# shema.net
KiCad netlist of a schematic drawn in EAGLE
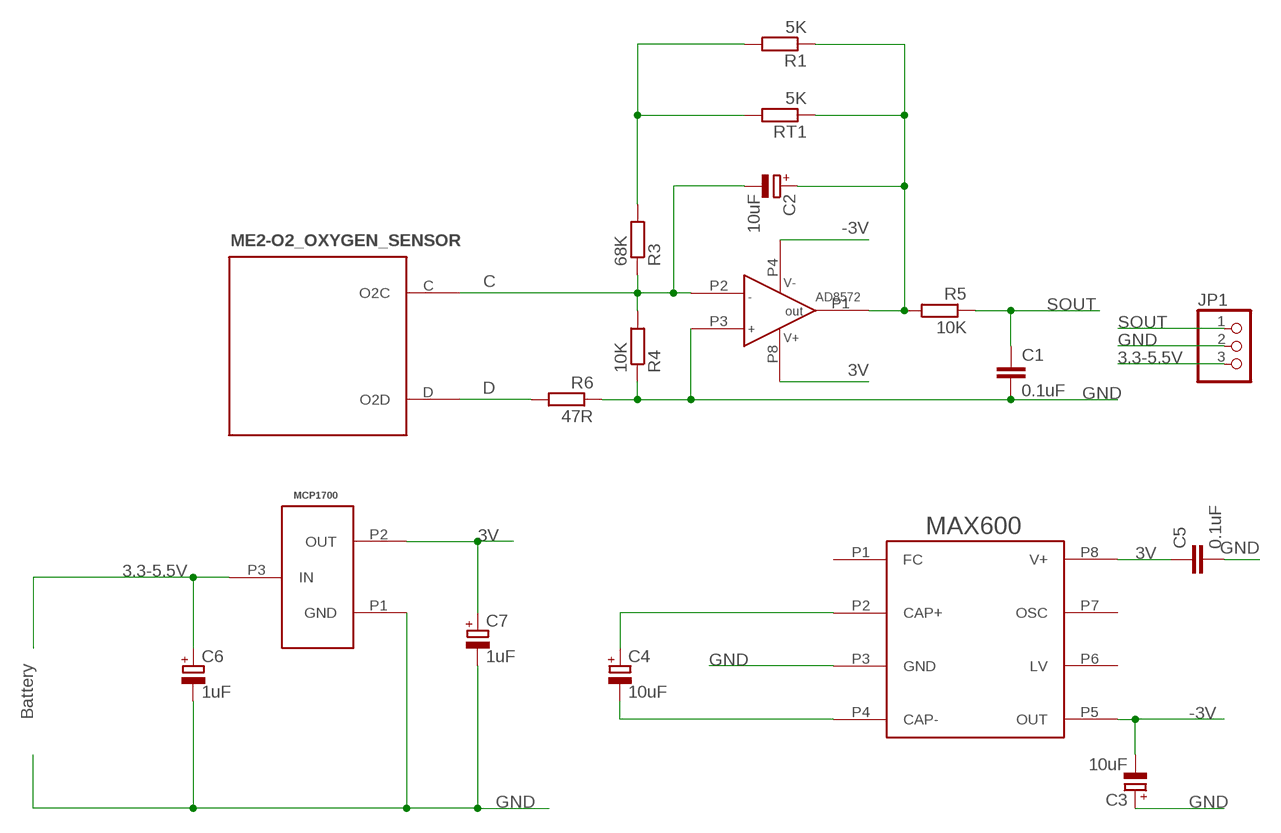
[diagram p0: schematic, sheet 1]

(export (version "E")
  (design (tool "Eeschema 10.0.6"))
  (components
    (comp (ref "AD8572")
      (value "AD8572")
      (footprint "eagle-import:AD8572")
      (libsource (lib "eagle-import") (part "AD8572"))
    )
    (comp (ref "C1")
      (value "0.1uF")
      (footprint "eagle-import:C0603")
      (libsource (lib "eagle-import") (part "C-EUC0603"))
    )
    (comp (ref "C2")
      (value "10uF")
      (footprint "eagle-import:153CLV-0405")
      (libsource (lib "eagle-import") (part "CPOL-EU153CLV-0405"))
    )
    (comp (ref "C3")
      (value "10uF")
      (footprint "eagle-import:153CLV-0405")
      (libsource (lib "eagle-import") (part "CPOL-EU153CLV-0405"))
    )
    (comp (ref "C4")
      (value "10uF")
      (footprint "eagle-import:153CLV-0405")
      (libsource (lib "eagle-import") (part "CPOL-EU153CLV-0405"))
    )
    (comp (ref "C5")
      (value "0.1uF")
      (footprint "eagle-import:C0603")
      (libsource (lib "eagle-import") (part "C-EUC0603"))
    )
    (comp (ref "C6")
      (value "1uF")
      (footprint "eagle-import:153CLV-0405")
      (libsource (lib "eagle-import") (part "CPOL-EU153CLV-0405"))
    )
    (comp (ref "C7")
      (value "1uF")
      (footprint "eagle-import:153CLV-0405")
      (libsource (lib "eagle-import") (part "CPOL-EU153CLV-0405"))
    )
    (comp (ref "JP1")
      (value "PINHD-1X3")
      (footprint "eagle-import:1X03")
      (libsource (lib "eagle-import") (part "PINHD-1X3"))
    )
    (comp (ref "MAX600")
      (value "MAX660")
      (footprint "eagle-import:MAX660")
      (libsource (lib "eagle-import") (part "MAX660"))
    )
    (comp (ref "MCP1700")
      (value "MCP1700")
      (footprint "eagle-import:MCP1700")
      (libsource (lib "eagle-import") (part "MCP1700"))
    )
    (comp (ref "ME2-O2_OXYGEN_SENSOR")
      (value "ME2-O2_OXYGEN_SENSOR")
      (footprint "eagle-import:ME2-O2_OXYGEN_SENSOR")
      (libsource (lib "eagle-import") (part "ME2-O2_OXYGEN_SENSOR"))
    )
    (comp (ref "R1")
      (value "5K")
      (footprint "eagle-import:R0603")
      (libsource (lib "eagle-import") (part "R-EU_R0603"))
    )
    (comp (ref "R3")
      (value "68K")
      (footprint "eagle-import:R0603")
      (libsource (lib "eagle-import") (part "R-EU_R0603"))
    )
    (comp (ref "R4")
      (value "10K")
      (footprint "eagle-import:R0603")
      (libsource (lib "eagle-import") (part "R-EU_R0603"))
    )
    (comp (ref "R5")
      (value "10K")
      (footprint "eagle-import:R0603")
      (libsource (lib "eagle-import") (part "R-EU_R0603"))
    )
    (comp (ref "R6")
      (value "47R")
      (footprint "eagle-import:R0603")
      (libsource (lib "eagle-import") (part "R-EU_R0603"))
    )
    (comp (ref "RT1")
      (value "5K")
      (footprint "eagle-import:R0603")
      (libsource (lib "eagle-import") (part "R-EU_R0603"))
    )
  )
  (nets
    (net (code "1") (name "/-3V") (class "Default")
      (node (ref "AD8572") (pin "P4") (pinfunction "V-_P4") (pintype "bidirectional"))
      (node (ref "C3") (pin "-") (pinfunction "-_-") (pintype "passive"))
      (node (ref "MAX600") (pin "P5") (pinfunction "OUT_P5") (pintype "bidirectional"))
    )
    (net (code "2") (name "/3.3-5.5V") (class "Default")
      (node (ref "C6") (pin "+") (pinfunction "+_+") (pintype "passive"))
      (node (ref "JP1") (pin "3") (pinfunction "3_3") (pintype "passive"))
      (node (ref "MCP1700") (pin "P3") (pinfunction "IN_P3") (pintype "bidirectional"))
    )
    (net (code "3") (name "/3V") (class "Default")
      (node (ref "AD8572") (pin "P8") (pinfunction "V+_P8") (pintype "bidirectional"))
      (node (ref "C5") (pin "1") (pinfunction "1_1") (pintype "passive"))
      (node (ref "C7") (pin "+") (pinfunction "+_+") (pintype "passive"))
      (node (ref "MAX600") (pin "P8") (pinfunction "V+_P8") (pintype "bidirectional"))
      (node (ref "MCP1700") (pin "P2") (pinfunction "OUT_P2") (pintype "bidirectional"))
    )
    (net (code "4") (name "/C") (class "Default")
      (node (ref "AD8572") (pin "P2") (pinfunction "-IN_P2") (pintype "bidirectional"))
      (node (ref "C2") (pin "-") (pinfunction "-_-") (pintype "passive"))
      (node (ref "ME2-O2_OXYGEN_SENSOR") (pin "C") (pinfunction "O2C_C") (pintype "bidirectional"))
      (node (ref "R3") (pin "1") (pinfunction "1_1") (pintype "passive"))
      (node (ref "R4") (pin "2") (pinfunction "2_2") (pintype "passive"))
    )
    (net (code "5") (name "/D") (class "Default")
      (node (ref "ME2-O2_OXYGEN_SENSOR") (pin "D") (pinfunction "O2D_D") (pintype "bidirectional"))
      (node (ref "R6") (pin "2") (pinfunction "2_2") (pintype "passive"))
    )
    (net (code "6") (name "/GND") (class "Default")
      (node (ref "AD8572") (pin "P3") (pinfunction "+IN_P3") (pintype "bidirectional"))
      (node (ref "C1") (pin "2") (pinfunction "2_2") (pintype "passive"))
      (node (ref "C3") (pin "+") (pinfunction "+_+") (pintype "passive"))
      (node (ref "C5") (pin "2") (pinfunction "2_2") (pintype "passive"))
      (node (ref "C6") (pin "-") (pinfunction "-_-") (pintype "passive"))
      (node (ref "C7") (pin "-") (pinfunction "-_-") (pintype "passive"))
      (node (ref "JP1") (pin "2") (pinfunction "2_2") (pintype "passive"))
      (node (ref "MAX600") (pin "P3") (pinfunction "GND_P3") (pintype "bidirectional"))
      (node (ref "MCP1700") (pin "P1") (pinfunction "GND_P1") (pintype "bidirectional"))
      (node (ref "R4") (pin "1") (pinfunction "1_1") (pintype "passive"))
      (node (ref "R6") (pin "1") (pinfunction "1_1") (pintype "passive"))
    )
    (net (code "7") (name "/SOUT") (class "Default")
      (node (ref "C1") (pin "1") (pinfunction "1_1") (pintype "passive"))
      (node (ref "JP1") (pin "1") (pinfunction "1_1") (pintype "passive"))
      (node (ref "R5") (pin "1") (pinfunction "1_1") (pintype "passive"))
    )
    (net (code "8") (name "Net-(AD8572-OUT)") (class "Default")
      (node (ref "AD8572") (pin "P1") (pinfunction "OUT_P1") (pintype "bidirectional"))
      (node (ref "C2") (pin "+") (pinfunction "+_+") (pintype "passive"))
      (node (ref "R1") (pin "1") (pinfunction "1_1") (pintype "passive"))
      (node (ref "R5") (pin "2") (pinfunction "2_2") (pintype "passive"))
      (node (ref "RT1") (pin "1") (pinfunction "1_1") (pintype "passive"))
    )
    (net (code "9") (name "Net-(MAX600-CAP+)") (class "Default")
      (node (ref "C4") (pin "+") (pinfunction "+_+") (pintype "passive"))
      (node (ref "MAX600") (pin "P2") (pinfunction "CAP+_P2") (pintype "bidirectional"))
    )
    (net (code "10") (name "Net-(MAX600-CAP-)") (class "Default")
      (node (ref "C4") (pin "-") (pinfunction "-_-") (pintype "passive"))
      (node (ref "MAX600") (pin "P4") (pinfunction "CAP-_P4") (pintype "bidirectional"))
    )
    (net (code "11") (name "Net-(R1-Pad2)") (class "Default")
      (node (ref "R1") (pin "2") (pinfunction "2_2") (pintype "passive"))
      (node (ref "R3") (pin "2") (pinfunction "2_2") (pintype "passive"))
      (node (ref "RT1") (pin "2") (pinfunction "2_2") (pintype "passive"))
    )
    (net (code "12") (name "unconnected-(MAX600-FC-PadP1)") (class "Default")
      (node (ref "MAX600") (pin "P1") (pinfunction "FC_P1") (pintype "bidirectional"))
    )
    (net (code "13") (name "unconnected-(MAX600-LV-PadP6)") (class "Default")
      (node (ref "MAX600") (pin "P6") (pinfunction "LV_P6") (pintype "bidirectional"))
    )
    (net (code "14") (name "unconnected-(MAX600-OSC-PadP7)") (class "Default")
      (node (ref "MAX600") (pin "P7") (pinfunction "OSC_P7") (pintype "bidirectional"))
    )
  )
)
